# Bootloader_Helper.net
KiCad netlist of a schematic drawn in EAGLE
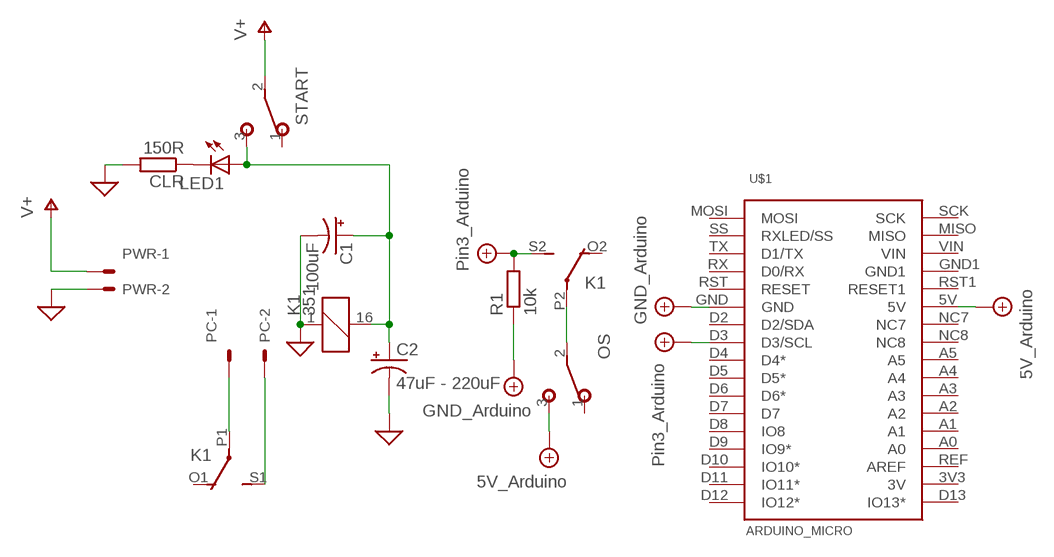
[diagram p0: schematic, sheet 1]

(export (version "E")
  (design (tool "Eeschema 10.0.6"))
  (components
    (comp (ref "C1")
      (value "100uF")
      (footprint "eagle-import:E2-4")
      (libsource (lib "eagle-import") (part "CPOL-USE2-4"))
    )
    (comp (ref "C2")
      (value "47uF - 220uF")
      (footprint "eagle-import:E2,5-7")
      (libsource (lib "eagle-import") (part "CPOL-USE2.5-7"))
    )
    (comp (ref "CLR")
      (value "150R")
      (footprint "eagle-import:0204_7")
      (libsource (lib "eagle-import") (part "R-EU_0204/7"))
    )
    (comp (ref "K1")
      (value "351")
      (footprint "eagle-import:351")
      (libsource (lib "eagle-import") (part "351"))
    )
    (comp (ref "LED1")
      (value "LED5MM")
      (footprint "eagle-import:LED5MM")
      (libsource (lib "eagle-import") (part "LED5MM"))
    )
    (comp (ref "OS")
      (value "SPDTPADS")
      (footprint "eagle-import:SPDT")
      (libsource (lib "eagle-import") (part "SPDTPADS"))
    )
    (comp (ref "PC")
      (value "ext. Power")
      (footprint "eagle-import:22-23-2021")
      (fields (field (name "MF") "MOLEX") (field (name "MPN") "22-23-2021"))
      (libsource (lib "eagle-import") (part "22-23-2021"))
    )
    (comp (ref "PWR")
      (value "ext. Power")
      (footprint "eagle-import:22-23-2021")
      (fields (field (name "MF") "MOLEX") (field (name "MPN") "22-23-2021"))
      (libsource (lib "eagle-import") (part "22-23-2021"))
    )
    (comp (ref "R1")
      (value "10k")
      (footprint "eagle-import:0204_7")
      (libsource (lib "eagle-import") (part "R-EU_0204/7"))
    )
    (comp (ref "START")
      (value "SPDTPADS")
      (footprint "eagle-import:SPDT")
      (libsource (lib "eagle-import") (part "SPDTPADS"))
    )
    (comp (ref "U$1")
      (value "ARDUINO_MICRO")
      (footprint "eagle-import:ARDUINO-MICRO")
      (libsource (lib "eagle-import") (part "ARDUINO_MICROFOOTPRINT"))
    )
  )
  (nets
    (net (code "1") (name "5V_Arduino") (class "Default")
      (node (ref "OS") (pin "3") (pinfunction "S_3") (pintype "passive"))
      (node (ref "U$1") (pin "5V") (pinfunction "5V_5V") (pintype "bidirectional"))
    )
    (net (code "2") (name "GND_Arduino") (class "Default")
      (node (ref "R1") (pin "1") (pinfunction "1_1") (pintype "passive"))
      (node (ref "U$1") (pin "GND") (pinfunction "GND_GND") (pintype "bidirectional"))
    )
    (net (code "3") (name "Net-(K1A-2)") (class "Default")
      (node (ref "C1") (pin "+") (pinfunction "+_+") (pintype "passive"))
      (node (ref "C2") (pin "+") (pinfunction "+_+") (pintype "passive"))
      (node (ref "K1") (pin "16") (pinfunction "2_16") (pintype "passive"))
      (node (ref "LED1") (pin "A") (pinfunction "A_A") (pintype "passive"))
      (node (ref "START") (pin "3") (pinfunction "S_3") (pintype "passive"))
    )
    (net (code "4") (name "Net-(K1B-P)") (class "Default")
      (node (ref "K1") (pin "P1") (pinfunction "P_P1") (pintype "passive"))
      (node (ref "PC") (pin "1") (pinfunction "S_1") (pintype "passive"))
    )
    (net (code "5") (name "Net-(K1B-S)") (class "Default")
      (node (ref "K1") (pin "S1") (pinfunction "S_S1") (pintype "passive"))
      (node (ref "PC") (pin "2") (pinfunction "S_2") (pintype "passive"))
    )
    (net (code "6") (name "Net-(K1C-P)") (class "Default")
      (node (ref "K1") (pin "P2") (pinfunction "P_P2") (pintype "passive"))
      (node (ref "OS") (pin "2") (pinfunction "P_2") (pintype "passive"))
    )
    (net (code "7") (name "Net-(LED1-C)") (class "Default")
      (node (ref "CLR") (pin "1") (pinfunction "1_1") (pintype "passive"))
      (node (ref "LED1") (pin "K") (pinfunction "C_K") (pintype "passive"))
    )
    (net (code "8") (name "Pin3_Arduino") (class "Default")
      (node (ref "K1") (pin "S2") (pinfunction "S_S2") (pintype "passive"))
      (node (ref "R1") (pin "2") (pinfunction "2_2") (pintype "passive"))
      (node (ref "U$1") (pin "D3") (pinfunction "D3/SCL_D3") (pintype "bidirectional"))
    )
    (net (code "9") (name "SUP") (class "Default")
      (node (ref "C1") (pin "-") (pinfunction "-_-") (pintype "passive"))
      (node (ref "C2") (pin "-") (pinfunction "-_-") (pintype "passive"))
      (node (ref "CLR") (pin "2") (pinfunction "2_2") (pintype "passive"))
      (node (ref "K1") (pin "1") (pinfunction "1_1") (pintype "passive"))
      (node (ref "PWR") (pin "2") (pinfunction "S_2") (pintype "passive"))
    )
    (net (code "10") (name "V+") (class "Default")
      (node (ref "PWR") (pin "1") (pinfunction "S_1") (pintype "passive"))
      (node (ref "START") (pin "2") (pinfunction "P_2") (pintype "passive"))
    )
    (net (code "11") (name "unconnected-(K1B-O-PadO1)") (class "Default")
      (node (ref "K1") (pin "O1") (pinfunction "O_O1") (pintype "passive"))
    )
    (net (code "12") (name "unconnected-(K1C-O-PadO2)") (class "Default")
      (node (ref "K1") (pin "O2") (pinfunction "O_O2") (pintype "passive"))
    )
    (net (code "13") (name "unconnected-(OS-O-Pad1)") (class "Default")
      (node (ref "OS") (pin "1") (pinfunction "O_1") (pintype "passive"))
    )
    (net (code "14") (name "unconnected-(START-O-Pad1)") (class "Default")
      (node (ref "START") (pin "1") (pinfunction "O_1") (pintype "passive"))
    )
    (net (code "15") (name "unconnected-(U$1-3V-Pad3V3)") (class "Default")
      (node (ref "U$1") (pin "3V3") (pinfunction "3V_3V3") (pintype "bidirectional"))
    )
    (net (code "16") (name "unconnected-(U$1-AREF-PadREF)") (class "Default")
      (node (ref "U$1") (pin "REF") (pinfunction "AREF_REF") (pintype "bidirectional"))
    )
    (net (code "17") (name "unconnected-(U$1-D0{slash}RX-PadRX)") (class "Default")
      (node (ref "U$1") (pin "RX") (pinfunction "D0/RX_RX") (pintype "bidirectional"))
    )
    (net (code "18") (name "unconnected-(U$1-D1{slash}TX-PadTX)") (class "Default")
      (node (ref "U$1") (pin "TX") (pinfunction "D1/TX_TX") (pintype "bidirectional"))
    )
    (net (code "19") (name "unconnected-(U$1-D2{slash}SDA-PadD2)") (class "Default")
      (node (ref "U$1") (pin "D2") (pinfunction "D2/SDA_D2") (pintype "bidirectional"))
    )
    (net (code "20") (name "unconnected-(U$1-D4*-PadD4)") (class "Default")
      (node (ref "U$1") (pin "D4") (pinfunction "D4*_D4") (pintype "bidirectional"))
    )
    (net (code "21") (name "unconnected-(U$1-D5*-PadD5)") (class "Default")
      (node (ref "U$1") (pin "D5") (pinfunction "D5*_D5") (pintype "bidirectional"))
    )
    (net (code "22") (name "unconnected-(U$1-D6*-PadD6)") (class "Default")
      (node (ref "U$1") (pin "D6") (pinfunction "D6*_D6") (pintype "bidirectional"))
    )
    (net (code "23") (name "unconnected-(U$1-IO8-PadD8)") (class "Default")
      (node (ref "U$1") (pin "D8") (pinfunction "IO8_D8") (pintype "bidirectional"))
    )
    (net (code "24") (name "unconnected-(U$1-IO9*-PadD9)") (class "Default")
      (node (ref "U$1") (pin "D9") (pinfunction "IO9*_D9") (pintype "bidirectional"))
    )
    (net (code "25") (name "unconnected-(U$1-IO10*-PadD10)") (class "Default")
      (node (ref "U$1") (pin "D10") (pinfunction "IO10*_D10") (pintype "bidirectional"))
    )
    (net (code "26") (name "unconnected-(U$1-IO11*-PadD11)") (class "Default")
      (node (ref "U$1") (pin "D11") (pinfunction "IO11*_D11") (pintype "bidirectional"))
    )
    (net (code "27") (name "unconnected-(U$1-IO12*-PadD12)") (class "Default")
      (node (ref "U$1") (pin "D12") (pinfunction "IO12*_D12") (pintype "bidirectional"))
    )
    (net (code "28") (name "unconnected-(U$1-IO13*-PadD13)") (class "Default")
      (node (ref "U$1") (pin "D13") (pinfunction "IO13*_D13") (pintype "bidirectional"))
    )
    (net (code "29") (name "unconnected-(U$1-PadA0)") (class "Default")
      (node (ref "U$1") (pin "A0") (pinfunction "A0_A0") (pintype "bidirectional"))
    )
    (net (code "30") (name "unconnected-(U$1-PadA1)") (class "Default")
      (node (ref "U$1") (pin "A1") (pinfunction "A1_A1") (pintype "bidirectional"))
    )
    (net (code "31") (name "unconnected-(U$1-PadA2)") (class "Default")
      (node (ref "U$1") (pin "A2") (pinfunction "A2_A2") (pintype "bidirectional"))
    )
    (net (code "32") (name "unconnected-(U$1-PadA3)") (class "Default")
      (node (ref "U$1") (pin "A3") (pinfunction "A3_A3") (pintype "bidirectional"))
    )
    (net (code "33") (name "unconnected-(U$1-PadA4)") (class "Default")
      (node (ref "U$1") (pin "A4") (pinfunction "A4_A4") (pintype "bidirectional"))
    )
    (net (code "34") (name "unconnected-(U$1-PadA5)") (class "Default")
      (node (ref "U$1") (pin "A5") (pinfunction "A5_A5") (pintype "bidirectional"))
    )
    (net (code "35") (name "unconnected-(U$1-PadD7)") (class "Default")
      (node (ref "U$1") (pin "D7") (pinfunction "D7_D7") (pintype "bidirectional"))
    )
    (net (code "36") (name "unconnected-(U$1-PadGND1)") (class "Default")
      (node (ref "U$1") (pin "GND1") (pinfunction "GND1_GND1") (pintype "bidirectional"))
    )
    (net (code "37") (name "unconnected-(U$1-PadMISO)") (class "Default")
      (node (ref "U$1") (pin "MISO") (pinfunction "MISO_MISO") (pintype "bidirectional"))
    )
    (net (code "38") (name "unconnected-(U$1-PadMOSI)") (class "Default")
      (node (ref "U$1") (pin "MOSI") (pinfunction "MOSI_MOSI") (pintype "bidirectional"))
    )
    (net (code "39") (name "unconnected-(U$1-PadNC7)") (class "Default")
      (node (ref "U$1") (pin "NC7") (pinfunction "NC7_NC7") (pintype "bidirectional"))
    )
    (net (code "40") (name "unconnected-(U$1-PadNC8)") (class "Default")
      (node (ref "U$1") (pin "NC8") (pinfunction "NC8_NC8") (pintype "bidirectional"))
    )
    (net (code "41") (name "unconnected-(U$1-PadSCK)") (class "Default")
      (node (ref "U$1") (pin "SCK") (pinfunction "SCK_SCK") (pintype "bidirectional"))
    )
    (net (code "42") (name "unconnected-(U$1-PadVIN)") (class "Default")
      (node (ref "U$1") (pin "VIN") (pinfunction "VIN_VIN") (pintype "bidirectional"))
    )
    (net (code "43") (name "unconnected-(U$1-RESET-PadRST)") (class "Default")
      (node (ref "U$1") (pin "RST") (pinfunction "RESET_RST") (pintype "bidirectional"))
    )
    (net (code "44") (name "unconnected-(U$1-RESET1-PadRST1)") (class "Default")
      (node (ref "U$1") (pin "RST1") (pinfunction "RESET1_RST1") (pintype "bidirectional"))
    )
    (net (code "45") (name "unconnected-(U$1-RXLED{slash}SS-PadSS)") (class "Default")
      (node (ref "U$1") (pin "SS") (pinfunction "RXLED/SS_SS") (pintype "bidirectional"))
    )
  )
)
